# SDR1806.net
KiCad netlist of a schematic drawn in EAGLE
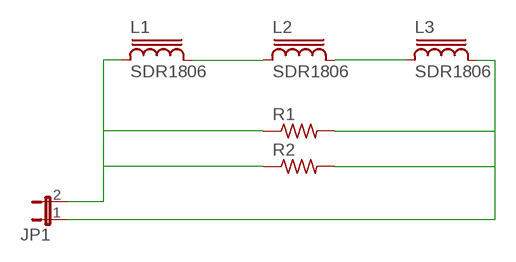
[diagram p0: schematic, sheet 1]

(export (version "E")
  (design (tool "Eeschema 10.0.6"))
  (components
    (comp (ref "JP1")
      (value "JP1E")
      (footprint "eagle-import:JP1")
      (libsource (lib "eagle-import") (part "JP1E"))
    )
    (comp (ref "L1")
      (value "SDR1806")
      (footprint "eagle-import:SDR1806")
      (libsource (lib "eagle-import") (part "SDR1806"))
    )
    (comp (ref "L2")
      (value "SDR1806")
      (footprint "eagle-import:SDR1806")
      (libsource (lib "eagle-import") (part "SDR1806"))
    )
    (comp (ref "L3")
      (value "SDR1806")
      (footprint "eagle-import:SDR1806")
      (libsource (lib "eagle-import") (part "SDR1806"))
    )
    (comp (ref "R1")
      (value "R-US_R0603")
      (footprint "eagle-import:R0603")
      (libsource (lib "eagle-import") (part "R-US_R0603"))
    )
    (comp (ref "R2")
      (value "R-US_R0603")
      (footprint "eagle-import:R0603")
      (libsource (lib "eagle-import") (part "R-US_R0603"))
    )
  )
  (nets
    (net (code "1") (name "Net-(JP1-Pad1)") (class "Default")
      (node (ref "JP1") (pin "1") (pinfunction "1_1") (pintype "passive"))
      (node (ref "L3") (pin "2") (pinfunction "2_2") (pintype "passive"))
      (node (ref "R1") (pin "2") (pinfunction "2_2") (pintype "passive"))
      (node (ref "R2") (pin "2") (pinfunction "2_2") (pintype "passive"))
    )
    (net (code "2") (name "Net-(JP1-Pad2)") (class "Default")
      (node (ref "JP1") (pin "2") (pinfunction "2_2") (pintype "passive"))
      (node (ref "L1") (pin "1") (pinfunction "1_1") (pintype "passive"))
      (node (ref "R1") (pin "1") (pinfunction "1_1") (pintype "passive"))
      (node (ref "R2") (pin "1") (pinfunction "1_1") (pintype "passive"))
    )
    (net (code "3") (name "Net-(L1-Pad2)") (class "Default")
      (node (ref "L1") (pin "2") (pinfunction "2_2") (pintype "passive"))
      (node (ref "L2") (pin "1") (pinfunction "1_1") (pintype "passive"))
    )
    (net (code "4") (name "Net-(L2-Pad2)") (class "Default")
      (node (ref "L2") (pin "2") (pinfunction "2_2") (pintype "passive"))
      (node (ref "L3") (pin "1") (pinfunction "1_1") (pintype "passive"))
    )
  )
)
